# NNP-DWG-165-001-000_BP2_Network_Interfac.net
KiCad netlist of a schematic drawn in Altium Designer
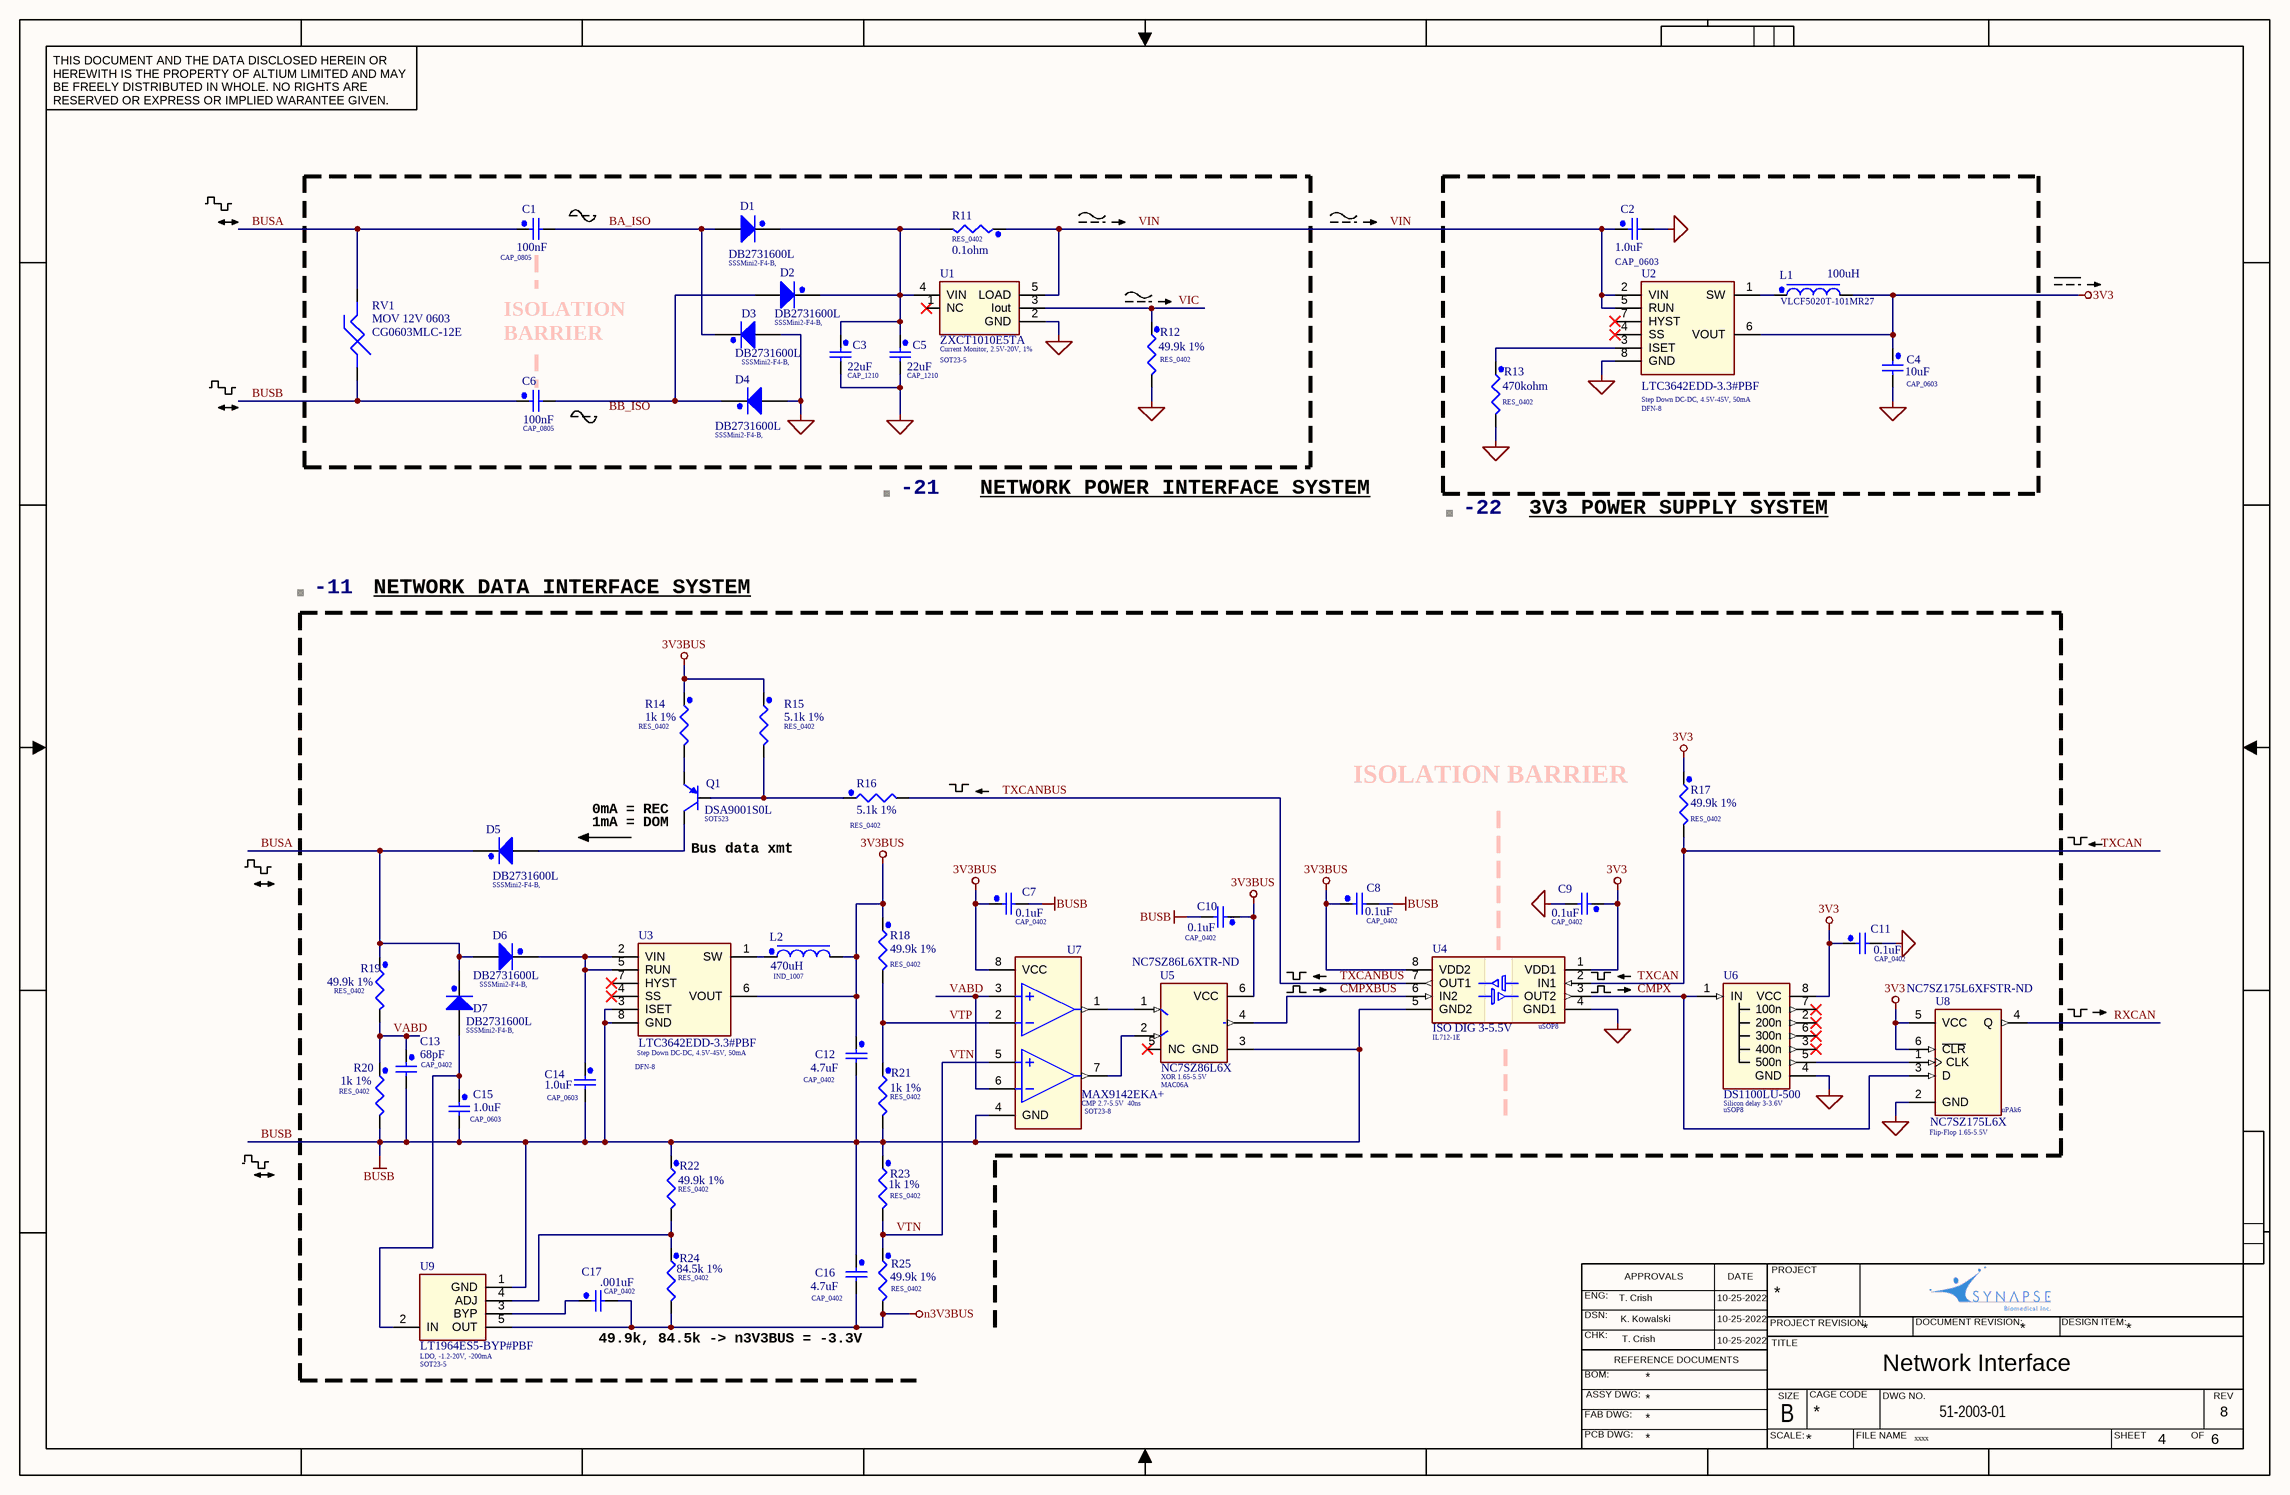
[diagram p0: NNP-DWG-165-001-000 BP2 Network Interface Pg 4 of 6.SchDoc]

(export (version "E")
  (design (tool "Eeschema 10.0.6"))
  (components
    (comp (ref "-11")
      (value "BOM_S1")
      (description "BOM item small graphic")
      (fields (field (name "XDESCRIPTION") "NETWORK DATA INTERFACE SYSTEM"))
      (libsource (lib "BOM_sym") (part "BOM_S1"))
    )
    (comp (ref "-21")
      (value "BOM_S1")
      (description "BOM item small graphic")
      (fields (field (name "XDESCRIPTION") "NETWORK POWER INTERFACE SYSTEM"))
      (libsource (lib "BOM_sym") (part "BOM_S1"))
    )
    (comp (ref "-22")
      (value "BOM_S1")
      (description "BOM item small graphic")
      (fields (field (name "XDESCRIPTION") "3V3 POWER SUPPLY SYSTEM"))
      (libsource (lib "BOM_sym") (part "BOM_S1"))
    )
    (comp (ref "C1")
      (value "100nF")
      (footprint "CAP_0805")
      (description "0.1uF, 100V, X7R, 0805, 10%, RoHS")
      (fields
        (field (name "MFR") "Murata Electronics North America")
        (field (name "PACKAGEDESCRIPTION") "CAP_0805")
        (field (name "MPN") "GRM155R71C104KA88D")
      )
      (libsource (lib "NNPS Integrated Parts") (part "GRM2165C2A101JA01D"))
    )
    (comp (ref "C2")
      (value "1.0uF")
      (footprint "CAP_0603")
      (description "1.0uF, 25V, X7R, 0603, 10%, RoHs")
      (fields
        (field (name "MFR") "TDK Corp")
        (field (name "PACKAGEDESCRIPTION") "CAP_0603")
        (field (name "MPN") "CGA3E1X7R1C105K080AC")
      )
      (libsource (lib "NNPS Integrated Parts") (part "GRM188R71E105KA12D"))
    )
    (comp (ref "C3")
      (value "22uF")
      (footprint "CHIP_1210N")
      (description "22uF, 16V, X5R, 1210, 20%, RoHS")
      (fields
        (field (name "MFR") "Samsung Electro-Mechanics America")
        (field (name "PACKAGEDESCRIPTION") "CAP_1210")
        (field (name "MPN") "CL32A226MOTLNNE")
      )
      (libsource (lib "NNPS Integrated Parts") (part "GRM32ER61C476ME15L"))
    )
    (comp (ref "C4")
      (value "10uF")
      (footprint "CAP_0603")
      (description "10uF, 6.3V, X5R, 0603_20%, RoHS")
      (fields
        (field (name "MFR") "Murata Electronics North America")
        (field (name "PACKAGEDESCRIPTION") "CAP_0603")
        (field (name "MPN") "GRM188R60J106ME47J")
      )
      (libsource (lib "NNPS Integrated Parts") (part "GRM188R60J106ME47J"))
    )
    (comp (ref "C5")
      (value "22uF")
      (footprint "CHIP_1210N")
      (description "22uF, 16V, X5R, 1210, 20%, RoHS")
      (fields
        (field (name "MFR") "Samsung Electro-Mechanics America")
        (field (name "PACKAGEDESCRIPTION") "CAP_1210")
        (field (name "MPN") "CL32A226MOTLNNE")
      )
      (libsource (lib "NNPS Integrated Parts") (part "GRM32ER61C476ME15L"))
    )
    (comp (ref "C6")
      (value "100nF")
      (footprint "CAP_0805")
      (description "0.1uF, 100V, X7R, 0805, 10%, RoHS")
      (fields
        (field (name "MFR") "Murata Electronics North America")
        (field (name "PACKAGEDESCRIPTION") "CAP_0805")
        (field (name "MPN") "GRM155R71C104KA88D")
      )
      (libsource (lib "NNPS Integrated Parts") (part "GRM2165C2A101JA01D"))
    )
    (comp (ref "C7")
      (value "0.1uF")
      (footprint "CAP_0402")
      (description "0.1uF, 16V, X7R, 0402, RoHS")
      (fields
        (field (name "MFR") "Murata Electronics North America")
        (field (name "PACKAGEDESCRIPTION") "CAP_0402")
        (field (name "MPN") "GRM155R71C104KA88D")
      )
      (libsource (lib "NNPS Integrated Parts") (part "GRM155R71C104KA88D"))
    )
    (comp (ref "C8")
      (value "0.1uF")
      (footprint "CAP_0402")
      (description "0.1uF, 16V, X7R, 0402, RoHS")
      (fields
        (field (name "MFR") "Murata Electronics North America")
        (field (name "PACKAGEDESCRIPTION") "CAP_0402")
        (field (name "MPN") "GRM155R71C104KA88D")
      )
      (libsource (lib "NNPS Integrated Parts") (part "GRM155R71C104KA88D"))
    )
    (comp (ref "C9")
      (value "0.1uF")
      (footprint "CAP_0402")
      (description "0.1uF, 16V, X7R, 0402, RoHS")
      (fields
        (field (name "MFR") "Murata Electronics North America")
        (field (name "PACKAGEDESCRIPTION") "CAP_0402")
        (field (name "MPN") "GRM155R71C104KA88D")
      )
      (libsource (lib "NNPS Integrated Parts") (part "GRM155R71C104KA88D"))
    )
    (comp (ref "C10")
      (value "0.1uF")
      (footprint "CAP_0402")
      (description "0.1uF, 16V, X7R, 0402, RoHS")
      (fields
        (field (name "MFR") "Murata Electronics North America")
        (field (name "PACKAGEDESCRIPTION") "CAP_0402")
        (field (name "MPN") "GRM155R71C104KA88D")
      )
      (libsource (lib "NNPS Integrated Parts") (part "GRM155R71C104KA88D"))
    )
    (comp (ref "C11")
      (value "0.1uF")
      (footprint "CAP_0402")
      (description "0.1uF, 16V, X7R, 0402, RoHS")
      (fields
        (field (name "MFR") "Murata Electronics North America")
        (field (name "PACKAGEDESCRIPTION") "CAP_0402")
        (field (name "MPN") "GRM155R71C104KA88D")
      )
      (libsource (lib "NNPS Integrated Parts") (part "GRM155R71C104KA88D"))
    )
    (comp (ref "C12")
      (value "4.7uF")
      (footprint "CAP_0402")
      (description "4.7uF, 6.3V, X5R, 20%, 0402, RoHS")
      (fields
        (field (name "MFR") "Murata Electronics North America")
        (field (name "PACKAGEDESCRIPTION") "CAP_0402")
        (field (name "MPN") "GRM155R60J475ME47D")
      )
      (libsource (lib "NNPS Integrated Parts") (part "ECJ-0EB0J475M"))
    )
    (comp (ref "C13")
      (value "68pF")
      (footprint "CAP_0402")
      (description "68pF, 50V, C0G, 0402, 5%, RoHS")
      (fields
        (field (name "MFR") "Murata Electronics  North America")
        (field (name "PACKAGEDESCRIPTION") "CAP_0402")
        (field (name "MPN") "GRM1555C1H680JA01D")
      )
      (libsource (lib "NNPS Integrated Parts") (part "GRM1555C1H680JZ01D"))
    )
    (comp (ref "C14")
      (value "1.0uF")
      (footprint "CAP_0603")
      (description "1.0uF, 25V, X7R, 0603, 10%, RoHs")
      (fields
        (field (name "MFR") "TDK Corp")
        (field (name "PACKAGEDESCRIPTION") "CAP_0603")
        (field (name "MPN") "CGA3E1X7R1C105K080AC")
      )
      (libsource (lib "NNPS Integrated Parts") (part "GRM188R71E105KA12D"))
    )
    (comp (ref "C15")
      (value "1.0uF")
      (footprint "CAP_0603")
      (description "1.0uF, 25V, X7R, 0603, 10%, RoHs")
      (fields
        (field (name "MFR") "TDK Corp")
        (field (name "PACKAGEDESCRIPTION") "CAP_0603")
        (field (name "MPN") "CGA3E1X7R1C105K080AC")
      )
      (libsource (lib "NNPS Integrated Parts") (part "GRM188R71E105KA12D"))
    )
    (comp (ref "C16")
      (value "4.7uF")
      (footprint "CAP_0402")
      (description "4.7uF, 6.3V, X5R, 20%, 0402, RoHS")
      (fields
        (field (name "MFR") "Murata Electronics North America")
        (field (name "PACKAGEDESCRIPTION") "CAP_0402")
        (field (name "MPN") "GRM155R60J475ME47D")
      )
      (libsource (lib "NNPS Integrated Parts") (part "ECJ-0EB0J475M"))
    )
    (comp (ref "C17")
      (value ".001uF")
      (footprint "CAP_0402")
      (description "0.001uF, 50V, X7R, 20%, 0402, RoHS")
      (fields
        (field (name "MFR") "Murata Electronics North America")
        (field (name "PACKAGEDESCRIPTION") "CAP_0402")
        (field (name "MPN") "GJM1555C1H1R0BB01D")
      )
      (libsource (lib "NNPS Integrated Parts") (part "C0402C103M5RACTU"))
    )
    (comp (ref "D1")
      (value "DB2731600L")
      (footprint "SSSMini2-F4-B")
      (description "Schotty Diode, 30V, 100mA, RoHS")
      (fields
        (field (name "MFR") "Panasonic Electronic Components")
        (field (name "PACKAGEDESCRIPTION") "SSSMini2-F4-B,")
      )
      (libsource (lib "NNPS Integrated Parts") (part "DB27316"))
    )
    (comp (ref "D2")
      (value "DB2731600L")
      (footprint "SSSMini2-F4-B")
      (description "Schotty Diode, 30V, 100mA, RoHS")
      (fields
        (field (name "MFR") "Panasonic Electronic Components")
        (field (name "PACKAGEDESCRIPTION") "SSSMini2-F4-B,")
      )
      (libsource (lib "NNPS Integrated Parts") (part "DB27316"))
    )
    (comp (ref "D3")
      (value "DB2731600L")
      (footprint "SSSMini2-F4-B")
      (description "Schotty Diode, 30V, 100mA, RoHS")
      (fields
        (field (name "MFR") "Panasonic Electronic Components")
        (field (name "PACKAGEDESCRIPTION") "SSSMini2-F4-B,")
      )
      (libsource (lib "NNPS Integrated Parts") (part "DB27316"))
    )
    (comp (ref "D4")
      (value "DB2731600L")
      (footprint "SSSMini2-F4-B")
      (description "Schotty Diode, 30V, 100mA, RoHS")
      (fields
        (field (name "MFR") "Panasonic Electronic Components")
        (field (name "PACKAGEDESCRIPTION") "SSSMini2-F4-B,")
      )
      (libsource (lib "NNPS Integrated Parts") (part "DB27316"))
    )
    (comp (ref "D5")
      (value "DB2731600L")
      (footprint "SSSMini2-F4-B")
      (description "Schotty Diode, 30V, 100mA, RoHS")
      (fields
        (field (name "MFR") "Panasonic Electronic Components")
        (field (name "PACKAGEDESCRIPTION") "SSSMini2-F4-B,")
      )
      (libsource (lib "NNPS Integrated Parts") (part "DB27316"))
    )
    (comp (ref "D6")
      (value "DB2731600L")
      (footprint "SSSMini2-F4-B")
      (description "Schotty Diode, 30V, 100mA, RoHS")
      (fields
        (field (name "MFR") "Panasonic Electronic Components")
        (field (name "PACKAGEDESCRIPTION") "SSSMini2-F4-B,")
      )
      (libsource (lib "NNPS Integrated Parts") (part "DB27316"))
    )
    (comp (ref "D7")
      (value "DB2731600L")
      (footprint "SSSMini2-F4-B")
      (description "Schotty Diode, 30V, 100mA, RoHS")
      (fields
        (field (name "MFR") "Panasonic Electronic Components")
        (field (name "PACKAGEDESCRIPTION") "SSSMini2-F4-B,")
      )
      (libsource (lib "NNPS Integrated Parts") (part "DB27316"))
    )
    (comp (ref "L1")
      (value "100uH")
      (footprint "IND LPS4414 COILCRAFT")
      (description "L_100u, 270mA, 20%, RoHS")
      (fields (field (name "MFR") "TDK Corporation") (field (name "MPN") "VLCF5020T-101MR27"))
      (libsource (lib "NNPS Integrated Parts") (part "VLCF5020T-101MR27"))
    )
    (comp (ref "L2")
      (value "470uH")
      (footprint "IND_1007")
      (description "470uH, 35mA, 10%, RoHS")
      (fields
        (field (name "MFR") "Taiyo Yuden")
        (field (name "PACKAGEDESCRIPTION") "IND_1007")
        (field (name "MPN") "CB2518T471K")
      )
      (libsource (lib "NNPS Integrated Parts") (part "CB2518T471K"))
    )
    (comp (ref "Q1")
      (value "DSA9001S0L")
      (footprint "SOT523")
      (description "PNP, -50V, -100mA, SOT523, 150MHz, RoHS")
      (fields
        (field (name "PACKAGEDESCRIPTION") "SOT523")
        (field (name "MFR") "Panasonic")
        (field (name "Comment") "Q_-50_-100m_SOT523")
      )
      (libsource (lib "NNPS Integrated Parts") (part "DSA9001"))
    )
    (comp (ref "R11")
      (value "0.1ohm")
      (footprint "RES_0402")
      (description "0.1 ohm, 1%, 1/16W, 0402, RoHS")
      (fields
        (field (name "MFR") "Susumu")
        (field (name "PACKAGEDESCRIPTION") "RES_0402")
        (field (name "MPN") "RP1005S-R10-F")
      )
      (libsource (lib "NNPS Integrated Parts") (part "RP1005S-R10-F"))
    )
    (comp (ref "R12")
      (value "49.9k 1%")
      (footprint "RES_0402")
      (description "49.9k ohm, 1%, 1/16W, 0402, RoHS")
      (fields
        (field (name "MFR") "Vishay Dale")
        (field (name "PACKAGEDESCRIPTION") "RES_0402")
        (field (name "MPN") "CRCW040249K9FKED")
      )
      (libsource (lib "NNPS Integrated Parts") (part "MCR01MZPF4992"))
    )
    (comp (ref "R13")
      (value "470kohm")
      (footprint "RES_0402")
      (description "470k ohm, 1% , 1/16W, smd, 0402, RoHS")
      (fields
        (field (name "MFR") "Vishay Dale")
        (field (name "PACKAGEDESCRIPTION") "RES_0402")
        (field (name "MPN") "CRCW0402470KFKED")
      )
      (libsource (lib "NNPS Integrated Parts") (part "ERJ-2RKF4703X"))
    )
    (comp (ref "R14")
      (value "1k 1%")
      (footprint "RES_0402")
      (description "1.0k ohm, 1%, 1/16W, smd, 0402, RoHS")
      (fields
        (field (name "MFR") "Vishay Dale")
        (field (name "PACKAGEDESCRIPTION") "RES_0402")
        (field (name "MPN") "CRCW04021K00FKED")
      )
      (libsource (lib "NNPS Integrated Parts") (part "MCR01MZPF1001"))
    )
    (comp (ref "R15")
      (value "5.1k 1%")
      (footprint "RES_0402")
      (description "5.1K ohm, 1%, 1/16W, smd, 0402, RoHS")
      (fields
        (field (name "MFR") "Vishay Dale")
        (field (name "PACKAGEDESCRIPTION") "RES_0402")
        (field (name "MPN") "CRCW04025K10FKED")
      )
      (libsource (lib "NNPS Integrated Parts") (part "MCR01MZPF5101"))
    )
    (comp (ref "R16")
      (value "5.1k 1%")
      (footprint "RES_0402")
      (description "5.1K ohm, 1%, 1/16W, smd, 0402, RoHS")
      (fields
        (field (name "MFR") "Vishay Dale")
        (field (name "PACKAGEDESCRIPTION") "RES_0402")
        (field (name "MPN") "CRCW04025K10FKED")
      )
      (libsource (lib "NNPS Integrated Parts") (part "MCR01MZPF5101"))
    )
    (comp (ref "R17")
      (value "49.9k 1%")
      (footprint "RES_0402")
      (description "49.9k ohm, 1%, 1/16W, 0402, RoHS")
      (fields
        (field (name "MFR") "Vishay Dale")
        (field (name "PACKAGEDESCRIPTION") "RES_0402")
        (field (name "MPN") "CRCW040249K9FKED")
      )
      (libsource (lib "NNPS Integrated Parts") (part "MCR01MZPF4992"))
    )
    (comp (ref "R18")
      (value "49.9k 1%")
      (footprint "RES_0402")
      (description "49.9k ohm, 1%, 1/16W, 0402, RoHS")
      (fields
        (field (name "MFR") "Vishay Dale")
        (field (name "PACKAGEDESCRIPTION") "RES_0402")
        (field (name "MPN") "CRCW040249K9FKED")
      )
      (libsource (lib "NNPS Integrated Parts") (part "MCR01MZPF4992"))
    )
    (comp (ref "R19")
      (value "49.9k 1%")
      (footprint "RES_0402")
      (description "49.9k ohm, 1%, 1/16W, 0402, RoHS")
      (fields
        (field (name "MFR") "Vishay Dale")
        (field (name "PACKAGEDESCRIPTION") "RES_0402")
        (field (name "MPN") "CRCW040249K9FKED")
      )
      (libsource (lib "NNPS Integrated Parts") (part "MCR01MZPF4992"))
    )
    (comp (ref "R20")
      (value "1k 1%")
      (footprint "RES_0402")
      (description "1.0k ohm, 1%, 1/16W, smd, 0402, RoHS")
      (fields
        (field (name "MFR") "Vishay Dale")
        (field (name "PACKAGEDESCRIPTION") "RES_0402")
        (field (name "MPN") "CRCW04021K00FKED")
      )
      (libsource (lib "NNPS Integrated Parts") (part "MCR01MZPF1001"))
    )
    (comp (ref "R21")
      (value "1k 1%")
      (footprint "RES_0402")
      (description "1.0k ohm, 1%, 1/16W, smd, 0402, RoHS")
      (fields
        (field (name "MFR") "Vishay Dale")
        (field (name "PACKAGEDESCRIPTION") "RES_0402")
        (field (name "MPN") "CRCW04021K00FKED")
      )
      (libsource (lib "NNPS Integrated Parts") (part "MCR01MZPF1001"))
    )
    (comp (ref "R22")
      (value "49.9k 1%")
      (footprint "RES_0402")
      (description "49.9k ohm, 1%, 1/16W, 0402, RoHS")
      (fields
        (field (name "MFR") "Vishay Dale")
        (field (name "PACKAGEDESCRIPTION") "RES_0402")
        (field (name "MPN") "CRCW040249K9FKED")
      )
      (libsource (lib "NNPS Integrated Parts") (part "MCR01MZPF4992"))
    )
    (comp (ref "R23")
      (value "1k 1%")
      (footprint "RES_0402")
      (description "1.0k ohm, 1%, 1/16W, smd, 0402, RoHS")
      (fields
        (field (name "MFR") "Vishay Dale")
        (field (name "PACKAGEDESCRIPTION") "RES_0402")
        (field (name "MPN") "CRCW04021K00FKED")
      )
      (libsource (lib "NNPS Integrated Parts") (part "MCR01MZPF1001"))
    )
    (comp (ref "R24")
      (value "84.5k 1%")
      (footprint "RES_0402")
      (description "84.5k ohm, 1%, 1/10W, 0402, RoHS")
      (fields
        (field (name "MFR") "Vishay Dale")
        (field (name "PACKAGEDESCRIPTION") "RES_0402")
        (field (name "MPN") "CRCW040284K5FKED")
      )
      (libsource (lib "NNPS Integrated Parts") (part "ERJ-2RKF8452X"))
    )
    (comp (ref "R25")
      (value "49.9k 1%")
      (footprint "RES_0402")
      (description "49.9k ohm, 1%, 1/16W, 0402, RoHS")
      (fields
        (field (name "MFR") "Vishay Dale")
        (field (name "PACKAGEDESCRIPTION") "RES_0402")
        (field (name "MPN") "CRCW040249K9FKED")
      )
      (libsource (lib "NNPS Integrated Parts") (part "MCR01MZPF4992"))
    )
    (comp (ref "RV1")
      (value "MOV 12V 0603")
      (footprint "RES_0603")
      (description "MOV, 12V, 0603, RoHS")
      (fields (field (name "MFR") "Bourns") (field (name "MPN") "CG0603MLC-12E"))
      (libsource (lib "NNPS Integrated Parts") (part "CG0603MLC-12E"))
    )
    (comp (ref "U1")
      (value "Current Monitor, 2.5V-20V, 1%")
      (footprint "SOT23-5")
      (description "Current Monitor, 2.5V-20V, 1%, RoHS")
      (fields
        (field (name "MFR") "Zetex")
        (field (name "PACKAGEDESCRIPTION") "SOT23-5")
        (field (name "MPN") "ZXCT1010E5TA")
      )
      (libsource (lib "NNPS Integrated Parts") (part "ZXCT1010E5TA"))
    )
    (comp (ref "U2")
      (value "Step Down DC-DC, 4.5V-45V, 50mA")
      (footprint "DFN8")
      (description "Step Down DC-DC, 4.5V-45V, 50mA, RoHS")
      (fields
        (field (name "PACKAGEDESCRIPTION") "DFN-8")
        (field (name "MFR") "Linear Technology")
        (field (name "MPN") "LTC3642EDD-3.3#PBF")
      )
      (libsource (lib "NNPS Integrated Parts") (part "LTC3642EDD"))
    )
    (comp (ref "U3")
      (value "Step Down DC-DC, 4.5V-45V, 50mA")
      (footprint "DFN8")
      (description "Step Down DC-DC, 4.5V-45V, 50mA, RoHS")
      (fields
        (field (name "PACKAGEDESCRIPTION") "DFN-8")
        (field (name "MFR") "Linear Technology")
        (field (name "MPN") "LTC3642EDD-3.3#PBF")
      )
      (libsource (lib "NNPS Integrated Parts") (part "LTC3642EDD"))
    )
    (comp (ref "U4")
      (value "ISO DIG 3-5.5V")
      (footprint "MSOP-8L")
      (description "Digital Isolator, 3-5.5V, uSOP8, RoHS")
      (fields
        (field (name "PACKAGEDESCRIPTION") "uSOP8")
        (field (name "MFR") "NVE")
        (field (name "MPN") "IL712-1E")
      )
      (libsource (lib "NNPS Integrated Parts") (part "IL712-1E"))
    )
    (comp (ref "U5")
      (value "XOR 1.65-5.5V")
      (footprint "uPak6")
      (description "XOR, 1.65-5.5V, uPAK6, RoHS")
      (fields
        (field (name "MFR") "Fairchild")
        (field (name "PACKAGEDESCRIPTION") "MAC06A")
        (field (name "MPN") "NC7SZ86L6X")
        (field (name "SUPPLIER PART NUMBER 1") "NC7SZ86L6XTR-ND")
      )
      (libsource (lib "NNPS Integrated Parts") (part "NC7SZ86L6X"))
    )
    (comp (ref "U6")
      (value "Silicon delay 3-3.6V")
      (footprint "MSOP-8L")
      (description "Silicon delay,  3-3.6V, uSOP8, RoHS")
      (fields
        (field (name "PACKAGEDESCRIPTION") "uSOP8")
        (field (name "MFR") "Maxim")
        (field (name "MPN") "DS1100LU-500")
      )
      (libsource (lib "NNPS Integrated Parts") (part "DS1100LU-500"))
    )
    (comp (ref "U7")
      (value "CMP 2.7-5.5V  40ns")
      (footprint "SOT23-8")
      (description "Comparator, 2.7-5.5V, 40nS, SOT23-8, RoHS")
      (fields
        (field (name "PACKAGEDESCRIPTION") "SOT23-8")
        (field (name "MFR") "Maxim")
        (field (name "MPN") "MAX9142EKA+")
      )
      (libsource (lib "NNPS Integrated Parts") (part "MAX9142EKA"))
    )
    (comp (ref "U8")
      (value "Flip-Flop 1.65-5.5V")
      (footprint "uPak6")
      (description "FLIPFLOP, 1.65-5.5V, uPAk6, RoHS")
      (fields
        (field (name "MFR") "Fairchild")
        (field (name "PACKAGEDESCRIPTION") "uPAk6")
        (field (name "MPN") "NC7SZ175L6X")
        (field (name "SUPPLIER PART NUMBER 1") "NC7SZ175L6XFSTR-ND")
      )
      (libsource (lib "NNPS Integrated Parts") (part "NC7SZ175L6X"))
    )
    (comp (ref "U9")
      (value "LDO, -1.2-20V, -200mA")
      (footprint "SOT23-5")
      (description "Low Droupout negative regulator, -5V, -200mA")
      (fields
        (field (name "PACKAGEDESCRIPTION") "SOT23-5")
        (field (name "MFR") "Linear Technology")
        (field (name "MPN") "LT1964ES5-BYP#PBF")
      )
      (libsource (lib "NNPS Integrated Parts") (part "LT1964ES5-BYP"))
    )
  )
  (nets
    (net (code "1") (name "/BA_ISO") (class "Default")
      (node (ref "C1") (pin "2") (pinfunction "2_2") (pintype "passive"))
      (node (ref "D1") (pin "2") (pinfunction "A_2") (pintype "passive"))
      (node (ref "D3") (pin "1") (pinfunction "C_1") (pintype "passive"))
    )
    (net (code "3") (name "/BUSA") (class "Default")
      (node (ref "C1") (pin "1") (pinfunction "1_1") (pintype "passive"))
      (node (ref "D5") (pin "1") (pinfunction "C_1") (pintype "passive"))
      (node (ref "D6") (pin "2") (pinfunction "A_2") (pintype "passive"))
      (node (ref "D7") (pin "1") (pinfunction "C_1") (pintype "passive"))
      (node (ref "R19") (pin "1") (pinfunction "1_1") (pintype "passive"))
      (node (ref "RV1") (pin "1") (pinfunction "P_1") (pintype "passive"))
    )
    (net (code "4") (name "/CMPX") (class "Default")
      (node (ref "U4") (pin "3") (pinfunction "OUT2_3") (pintype "output"))
      (node (ref "U6") (pin "1") (pinfunction "IN_1") (pintype "input"))
      (node (ref "U8") (pin "3") (pinfunction "D_3") (pintype "input"))
    )
    (net (code "5") (name "/CMPXBUS") (class "Default")
      (node (ref "U4") (pin "6") (pinfunction "IN2_6") (pintype "input"))
      (node (ref "U5") (pin "4") (pinfunction "O_4") (pintype "output"))
    )
    (net (code "6") (name "/RXCAN") (class "Default")
      (node (ref "U8") (pin "4") (pinfunction "Q_4") (pintype "output"))
    )
    (net (code "7") (name "/TXCAN") (class "Default")
      (node (ref "R17") (pin "2") (pinfunction "2_2") (pintype "passive"))
      (node (ref "U4") (pin "2") (pinfunction "IN1_2") (pintype "input"))
    )
    (net (code "8") (name "/TXCANBUS") (class "Default")
      (node (ref "R16") (pin "2") (pinfunction "2_2") (pintype "passive"))
      (node (ref "U4") (pin "7") (pinfunction "OUT1_7") (pintype "output"))
    )
    (net (code "9") (name "/VABD") (class "Default")
      (node (ref "C13") (pin "1") (pinfunction "1_1") (pintype "passive"))
      (node (ref "R19") (pin "2") (pinfunction "2_2") (pintype "passive"))
      (node (ref "R20") (pin "1") (pinfunction "1_1") (pintype "passive"))
      (node (ref "U7") (pin "3") (pinfunction "INA+_3") (pintype "tri_state"))
      (node (ref "U7") (pin "6") (pinfunction "INB-_6") (pintype "tri_state"))
    )
    (net (code "10") (name "/VIC") (class "Default")
      (node (ref "R12") (pin "1") (pinfunction "1_1") (pintype "passive"))
      (node (ref "U1") (pin "3") (pinfunction "Iout_3") (pintype "passive"))
    )
    (net (code "11") (name "/VIN") (class "Default")
      (node (ref "C2") (pin "1") (pinfunction "1_1") (pintype "passive"))
      (node (ref "R11") (pin "1") (pinfunction "1_1") (pintype "passive"))
      (node (ref "U1") (pin "5") (pinfunction "LOAD_5") (pintype "passive"))
      (node (ref "U2") (pin "2") (pinfunction "VIN_2") (pintype "passive"))
      (node (ref "U2") (pin "5") (pinfunction "RUN_5") (pintype "passive"))
    )
    (net (code "12") (name "/VTN") (class "Default")
      (node (ref "R23") (pin "2") (pinfunction "2_2") (pintype "passive"))
      (node (ref "R25") (pin "1") (pinfunction "1_1") (pintype "passive"))
      (node (ref "U7") (pin "5") (pinfunction "INB+_5") (pintype "tri_state"))
    )
    (net (code "13") (name "/VTP") (class "Default")
      (node (ref "R18") (pin "2") (pinfunction "2_2") (pintype "passive"))
      (node (ref "R21") (pin "1") (pinfunction "1_1") (pintype "passive"))
      (node (ref "U7") (pin "2") (pinfunction "INA-_2") (pintype "tri_state"))
    )
    (net (code "14") (name "3V3") (class "Default")
      (node (ref "C11") (pin "1") (pinfunction "1_1") (pintype "passive"))
      (node (ref "C4") (pin "1") (pinfunction "1_1") (pintype "passive"))
      (node (ref "C9") (pin "1") (pinfunction "1_1") (pintype "passive"))
      (node (ref "L1") (pin "2") (pinfunction "2_2") (pintype "passive"))
      (node (ref "R17") (pin "1") (pinfunction "1_1") (pintype "passive"))
      (node (ref "U2") (pin "6") (pinfunction "VOUT_6") (pintype "passive"))
      (node (ref "U4") (pin "1") (pinfunction "VDD1_1") (pintype "power_in"))
      (node (ref "U6") (pin "8") (pinfunction "VCC_8") (pintype "power_in"))
      (node (ref "U8") (pin "5") (pinfunction "VCC_5") (pintype "power_in"))
      (node (ref "U8") (pin "6") (pinfunction "CLR_6") (pintype "input"))
    )
    (net (code "15") (name "3V3BUS") (class "Default")
      (node (ref "C10") (pin "1") (pinfunction "1_1") (pintype "passive"))
      (node (ref "C12") (pin "1") (pinfunction "1_1") (pintype "passive"))
      (node (ref "C7") (pin "1") (pinfunction "1_1") (pintype "passive"))
      (node (ref "C8") (pin "1") (pinfunction "1_1") (pintype "passive"))
      (node (ref "L2") (pin "2") (pinfunction "2_2") (pintype "passive"))
      (node (ref "R14") (pin "1") (pinfunction "1_1") (pintype "passive"))
      (node (ref "R15") (pin "1") (pinfunction "1_1") (pintype "passive"))
      (node (ref "R18") (pin "1") (pinfunction "1_1") (pintype "passive"))
      (node (ref "U3") (pin "6") (pinfunction "VOUT_6") (pintype "passive"))
      (node (ref "U4") (pin "8") (pinfunction "VDD2_8") (pintype "power_in"))
      (node (ref "U5") (pin "6") (pinfunction "VCC_6") (pintype "power_in"))
      (node (ref "U7") (pin "8") (pinfunction "VCC_8") (pintype "power_in"))
    )
    (net (code "16") (name "BUSB") (class "Default")
      (node (ref "C10") (pin "2") (pinfunction "2_2") (pintype "passive"))
      (node (ref "C12") (pin "2") (pinfunction "2_2") (pintype "passive"))
      (node (ref "C13") (pin "2") (pinfunction "2_2") (pintype "passive"))
      (node (ref "C14") (pin "2") (pinfunction "2_2") (pintype "passive"))
      (node (ref "C15") (pin "2") (pinfunction "2_2") (pintype "passive"))
      (node (ref "C16") (pin "1") (pinfunction "1_1") (pintype "passive"))
      (node (ref "C6") (pin "1") (pinfunction "1_1") (pintype "passive"))
      (node (ref "C7") (pin "2") (pinfunction "2_2") (pintype "passive"))
      (node (ref "C8") (pin "2") (pinfunction "2_2") (pintype "passive"))
      (node (ref "R20") (pin "2") (pinfunction "2_2") (pintype "passive"))
      (node (ref "R21") (pin "2") (pinfunction "2_2") (pintype "passive"))
      (node (ref "R22") (pin "1") (pinfunction "1_1") (pintype "passive"))
      (node (ref "R23") (pin "1") (pinfunction "1_1") (pintype "passive"))
      (node (ref "RV1") (pin "2") (pinfunction "P_2") (pintype "passive"))
      (node (ref "U3") (pin "3") (pinfunction "ISET_3") (pintype "passive"))
      (node (ref "U3") (pin "8") (pinfunction "GND_8") (pintype "passive"))
      (node (ref "U4") (pin "5") (pinfunction "GND2_5") (pintype "power_in"))
      (node (ref "U5") (pin "3") (pinfunction "GND_3") (pintype "power_in"))
      (node (ref "U7") (pin "4") (pinfunction "GND_4") (pintype "power_in"))
      (node (ref "U9") (pin "1") (pinfunction "GND_1") (pintype "power_in"))
    )
    (net (code "17") (name "GND") (class "Default")
      (node (ref "C11") (pin "2") (pinfunction "2_2") (pintype "passive"))
      (node (ref "C2") (pin "2") (pinfunction "2_2") (pintype "passive"))
      (node (ref "C3") (pin "2") (pinfunction "2_2") (pintype "passive"))
      (node (ref "C4") (pin "2") (pinfunction "2_2") (pintype "passive"))
      (node (ref "C5") (pin "2") (pinfunction "2_2") (pintype "passive"))
      (node (ref "C9") (pin "2") (pinfunction "2_2") (pintype "passive"))
      (node (ref "D3") (pin "2") (pinfunction "A_2") (pintype "passive"))
      (node (ref "D4") (pin "2") (pinfunction "A_2") (pintype "passive"))
      (node (ref "R12") (pin "2") (pinfunction "2_2") (pintype "passive"))
      (node (ref "R13") (pin "2") (pinfunction "2_2") (pintype "passive"))
      (node (ref "U1") (pin "2") (pinfunction "GND_2") (pintype "power_in"))
      (node (ref "U2") (pin "8") (pinfunction "GND_8") (pintype "passive"))
      (node (ref "U4") (pin "4") (pinfunction "GND1_4") (pintype "power_in"))
      (node (ref "U6") (pin "4") (pinfunction "GND_4") (pintype "power_in"))
      (node (ref "U8") (pin "2") (pinfunction "GND_2") (pintype "power_in"))
    )
    (net (code "18") (name "Net-(D1-C)") (class "Default")
      (node (ref "C3") (pin "1") (pinfunction "1_1") (pintype "passive"))
      (node (ref "C5") (pin "1") (pinfunction "1_1") (pintype "passive"))
      (node (ref "D1") (pin "1") (pinfunction "C_1") (pintype "passive"))
      (node (ref "D2") (pin "1") (pinfunction "C_1") (pintype "passive"))
      (node (ref "R11") (pin "2") (pinfunction "2_2") (pintype "passive"))
      (node (ref "U1") (pin "4") (pinfunction "VIN_4") (pintype "power_in"))
    )
    (net (code "19") (name "Net-(D2-A)") (class "Default")
      (node (ref "C6") (pin "2") (pinfunction "2_2") (pintype "passive"))
      (node (ref "D2") (pin "2") (pinfunction "A_2") (pintype "passive"))
      (node (ref "D4") (pin "1") (pinfunction "C_1") (pintype "passive"))
    )
    (net (code "20") (name "Net-(D5-A)") (class "Default")
      (node (ref "D5") (pin "2") (pinfunction "A_2") (pintype "passive"))
      (node (ref "Q1") (pin "3") (pinfunction "C_3") (pintype "passive"))
    )
    (net (code "21") (name "Net-(D6-C)") (class "Default")
      (node (ref "C14") (pin "1") (pinfunction "1_1") (pintype "passive"))
      (node (ref "D6") (pin "1") (pinfunction "C_1") (pintype "passive"))
      (node (ref "U3") (pin "2") (pinfunction "VIN_2") (pintype "passive"))
      (node (ref "U3") (pin "5") (pinfunction "RUN_5") (pintype "passive"))
    )
    (net (code "22") (name "Net-(D7-A)") (class "Default")
      (node (ref "C15") (pin "1") (pinfunction "1_1") (pintype "passive"))
      (node (ref "D7") (pin "2") (pinfunction "A_2") (pintype "passive"))
      (node (ref "U9") (pin "2") (pinfunction "IN_2") (pintype "power_in"))
    )
    (net (code "23") (name "Net-(Q1-B)") (class "Default")
      (node (ref "Q1") (pin "1") (pinfunction "B_1") (pintype "passive"))
      (node (ref "R15") (pin "2") (pinfunction "2_2") (pintype "passive"))
      (node (ref "R16") (pin "1") (pinfunction "1_1") (pintype "passive"))
    )
    (net (code "24") (name "Net-(Q1-E)") (class "Default")
      (node (ref "Q1") (pin "2") (pinfunction "E_2") (pintype "passive"))
      (node (ref "R14") (pin "2") (pinfunction "2_2") (pintype "passive"))
    )
    (net (code "25") (name "Net-(U2-ISET)") (class "Default")
      (node (ref "R13") (pin "1") (pinfunction "1_1") (pintype "passive"))
      (node (ref "U2") (pin "3") (pinfunction "ISET_3") (pintype "passive"))
    )
    (net (code "26") (name "Net-(U2-SW)") (class "Default")
      (node (ref "L1") (pin "1") (pinfunction "1_1") (pintype "passive"))
      (node (ref "U2") (pin "1") (pinfunction "SW_1") (pintype "passive"))
    )
    (net (code "27") (name "Net-(U3-SW)") (class "Default")
      (node (ref "L2") (pin "1") (pinfunction "1_1") (pintype "passive"))
      (node (ref "U3") (pin "1") (pinfunction "SW_1") (pintype "passive"))
    )
    (net (code "28") (name "Net-(U5-A)") (class "Default")
      (node (ref "U5") (pin "1") (pinfunction "A_1") (pintype "input"))
      (node (ref "U7") (pin "1") (pinfunction "OUTA_1") (pintype "output"))
    )
    (net (code "29") (name "Net-(U5-B)") (class "Default")
      (node (ref "U5") (pin "2") (pinfunction "B_2") (pintype "input"))
      (node (ref "U7") (pin "7") (pinfunction "OUTB_7") (pintype "output"))
    )
    (net (code "30") (name "Net-(U6-500n)") (class "Default")
      (node (ref "U6") (pin "5") (pinfunction "500n_5") (pintype "output"))
      (node (ref "U8") (pin "1") (pinfunction "CLK_1") (pintype "input"))
    )
    (net (code "31") (name "Net-(U9-ADJ)") (class "Default")
      (node (ref "R22") (pin "2") (pinfunction "2_2") (pintype "passive"))
      (node (ref "R24") (pin "1") (pinfunction "1_1") (pintype "passive"))
      (node (ref "U9") (pin "4") (pinfunction "ADJ_4") (pintype "power_in"))
    )
    (net (code "32") (name "Net-(U9-BYP)") (class "Default")
      (node (ref "C17") (pin "1") (pinfunction "1_1") (pintype "passive"))
      (node (ref "U9") (pin "3") (pinfunction "BYP_3") (pintype "power_in"))
    )
    (net (code "33") (name "n3V3BUS") (class "Default")
      (node (ref "C16") (pin "2") (pinfunction "2_2") (pintype "passive"))
      (node (ref "C17") (pin "2") (pinfunction "2_2") (pintype "passive"))
      (node (ref "R24") (pin "2") (pinfunction "2_2") (pintype "passive"))
      (node (ref "R25") (pin "2") (pinfunction "2_2") (pintype "passive"))
      (node (ref "U9") (pin "5") (pinfunction "OUT_5") (pintype "power_in"))
    )
    (net (code "34") (name "unconnected-(U1-NC-Pad1)") (class "Default")
      (node (ref "U1") (pin "1") (pinfunction "NC_1") (pintype "tri_state+no_connect"))
    )
    (net (code "35") (name "unconnected-(U2-HYST-Pad7)") (class "Default")
      (node (ref "U2") (pin "7") (pinfunction "HYST_7") (pintype "passive+no_connect"))
    )
    (net (code "36") (name "unconnected-(U2-SS-Pad4)") (class "Default")
      (node (ref "U2") (pin "4") (pinfunction "SS_4") (pintype "passive+no_connect"))
    )
    (net (code "37") (name "unconnected-(U3-HYST-Pad7)") (class "Default")
      (node (ref "U3") (pin "7") (pinfunction "HYST_7") (pintype "passive+no_connect"))
    )
    (net (code "38") (name "unconnected-(U3-SS-Pad4)") (class "Default")
      (node (ref "U3") (pin "4") (pinfunction "SS_4") (pintype "passive+no_connect"))
    )
    (net (code "39") (name "unconnected-(U5-NC-Pad5)") (class "Default")
      (node (ref "U5") (pin "5") (pinfunction "NC_5") (pintype "power_in+no_connect"))
    )
    (net (code "40") (name "unconnected-(U6-100n-Pad7)") (class "Default")
      (node (ref "U6") (pin "7") (pinfunction "100n_7") (pintype "output+no_connect"))
    )
    (net (code "41") (name "unconnected-(U6-200n-Pad2)") (class "Default")
      (node (ref "U6") (pin "2") (pinfunction "200n_2") (pintype "output+no_connect"))
    )
    (net (code "42") (name "unconnected-(U6-300n-Pad6)") (class "Default")
      (node (ref "U6") (pin "6") (pinfunction "300n_6") (pintype "output+no_connect"))
    )
    (net (code "43") (name "unconnected-(U6-400n-Pad3)") (class "Default")
      (node (ref "U6") (pin "3") (pinfunction "400n_3") (pintype "output+no_connect"))
    )
  )
)
